# OLEDMiniFlyNRF.net
KiCad netlist of a schematic drawn in Altium Designer
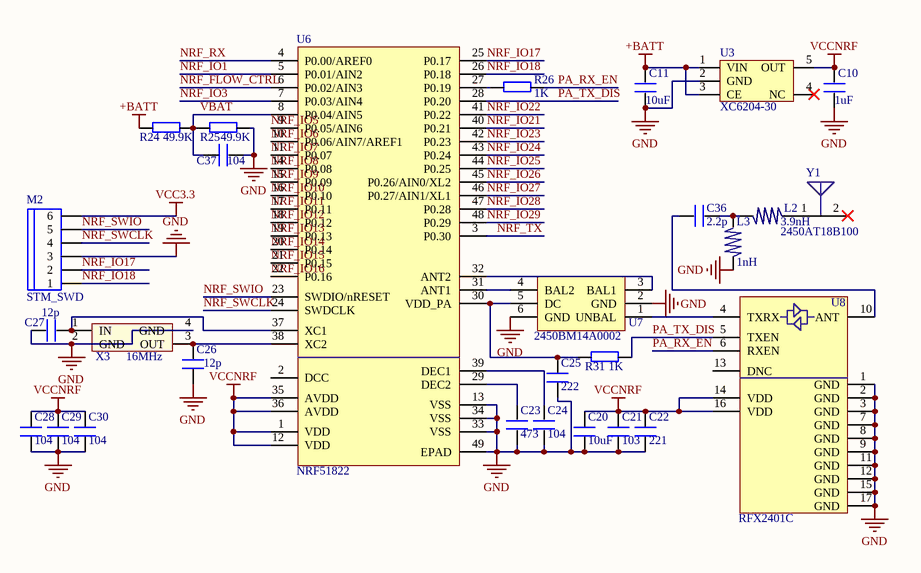
[diagram p0: OLEDMiniFlyNRF.SchDoc]

(export (version "E")
  (design (tool "Eeschema 10.0.6"))
  (components
    (comp (ref "C10") (value "1uF") (footprint "C 0603_L") (libsource (lib "ATK-2014-09-12") (part "C")))
    (comp (ref "C11") (value "10uF") (footprint "C 0603_L") (libsource (lib "ATK-2014-09-12") (part "C")))
    (comp (ref "C20") (value "10uF") (footprint "C 0603_L") (libsource (lib "ATK-2014-09-12") (part "C")))
    (comp (ref "C21") (value "103") (footprint "C 0603_L") (libsource (lib "ATK-2014-09-12") (part "C")))
    (comp (ref "C22") (value "221") (footprint "C 0603_L") (libsource (lib "ATK-2014-09-12") (part "C")))
    (comp (ref "C23") (value "473") (footprint "C 0603_L") (libsource (lib "ATK-2014-09-12") (part "C")))
    (comp (ref "C24") (value "104") (footprint "C 0603_L") (libsource (lib "ATK-2014-09-12") (part "C")))
    (comp (ref "C25") (value "222") (footprint "C 0603_L") (libsource (lib "ATK-2014-09-12") (part "C")))
    (comp (ref "C26") (value "12p") (footprint "C 0603_L") (libsource (lib "ATK-2014-09-12") (part "C")))
    (comp (ref "C27") (value "12p") (footprint "C 0603_L") (libsource (lib "ATK-2014-09-12") (part "C")))
    (comp (ref "C28") (value "104") (footprint "C 0603_L") (libsource (lib "ATK-2014-09-12") (part "C")))
    (comp (ref "C29") (value "104") (footprint "C 0603_L") (libsource (lib "ATK-2014-09-12") (part "C")))
    (comp (ref "C30") (value "104") (footprint "C 0603_L") (libsource (lib "ATK-2014-09-12") (part "C")))
    (comp (ref "C36") (value "2.2p") (footprint "0402") (libsource (lib "ATK-2014-09-12") (part "C")))
    (comp (ref "C37") (value "104") (footprint "C 0603_L") (libsource (lib "ATK-2014-09-12") (part "C")))
    (comp (ref "L2") (value "3.9nH") (footprint "0402") (libsource (lib "ATK-2014-09-12") (part "L")))
    (comp (ref "L3") (value "1nH") (footprint "0402") (libsource (lib "") (part "L_1")))
    (comp (ref "M2") (value "STM_SWD") (footprint "SH1.0_6P") (libsource (lib "MiniFly ") (part "HEAD6")))
    (comp (ref "R24") (value "49.9K") (footprint "R 0603_L") (libsource (lib "ATK-2014-09-12") (part "R")))
    (comp (ref "R25") (value "49.9K") (footprint "R 0603_L") (libsource (lib "ATK-2014-09-12") (part "R")))
    (comp (ref "R26") (value "1K") (footprint "R 0603_L") (libsource (lib "ATK-2014-09-12") (part "R")))
    (comp (ref "R31") (value "1K") (footprint "R 0603_L") (libsource (lib "ATK-2014-09-12") (part "R")))
    (comp (ref "U3")
      (value "XC6204-30")
      (footprint "SOT23-5L")
      (libsource (lib "ATK-2014-09-12") (part "XC6204"))
    )
    (comp (ref "U6")
      (value "NRF51822")
      (footprint "QFN48M-04")
      (libsource (lib "ATK-2014-09-12") (part "NRF51822"))
    )
    (comp (ref "U7")
      (value "2450BM14A0002")
      (footprint "0603-6")
      (libsource (lib "ATK-2014-09-12") (part "BALUN"))
    )
    (comp (ref "U8")
      (value "RFX2401C")
      (footprint "QFN16M")
      (libsource (lib "ATK-2014-09-12") (part "RFX2401C"))
    )
    (comp (ref "X3")
      (value "16MHz")
      (footprint "OSC32254Pmini")
      (description "无源贴片晶振")
      (libsource (lib "ATK-2014-09-12") (part "XTAL-无源贴片"))
    )
    (comp (ref "Y1")
      (value "2450AT18B100")
      (footprint "L 1206")
      (libsource (lib "ATK-2014-09-12") (part "CHIP_ANTENNA"))
    )
  )
  (nets
    (net (code "1") (name "+BATT") (class "Default")
      (node (ref "C11") (pin "2") (pintype "passive"))
      (node (ref "R24") (pin "2") (pintype "passive"))
      (node (ref "U3") (pin "1") (pinfunction "VIN_1") (pintype "passive"))
      (node (ref "U3") (pin "3") (pinfunction "CE_3") (pintype "passive"))
    )
    (net (code "2") (name "/NRF_FLOW_CTRL") (class "Default")
      (node (ref "U6") (pin "6") (pinfunction "P0.02/AIN3_6") (pintype "passive"))
    )
    (net (code "3") (name "/NRF_IO1") (class "Default")
      (node (ref "U6") (pin "5") (pinfunction "P0.01/AIN2_5") (pintype "passive"))
    )
    (net (code "4") (name "/NRF_IO3") (class "Default")
      (node (ref "U6") (pin "7") (pinfunction "P0.03/AIN4_7") (pintype "passive"))
    )
    (net (code "5") (name "/NRF_IO5") (class "Default")
      (node (ref "U6") (pin "9") (pinfunction "P0.05/AIN6_9") (pintype "passive"))
    )
    (net (code "6") (name "/NRF_IO6") (class "Default")
      (node (ref "U6") (pin "10") (pinfunction "P0.06/AIN7/AREF1_10") (pintype "passive"))
    )
    (net (code "7") (name "/NRF_IO7") (class "Default")
      (node (ref "U6") (pin "11") (pinfunction "P0.07_11") (pintype "passive"))
    )
    (net (code "8") (name "/NRF_IO8") (class "Default")
      (node (ref "U6") (pin "14") (pinfunction "P0.08_14") (pintype "passive"))
    )
    (net (code "9") (name "/NRF_IO9") (class "Default")
      (node (ref "U6") (pin "15") (pinfunction "P0.09_15") (pintype "passive"))
    )
    (net (code "10") (name "/NRF_IO10") (class "Default")
      (node (ref "U6") (pin "16") (pinfunction "P0.10_16") (pintype "passive"))
    )
    (net (code "11") (name "/NRF_IO11") (class "Default")
      (node (ref "U6") (pin "17") (pinfunction "P0.11_17") (pintype "passive"))
    )
    (net (code "12") (name "/NRF_IO12") (class "Default")
      (node (ref "U6") (pin "18") (pinfunction "P0.12_18") (pintype "passive"))
    )
    (net (code "13") (name "/NRF_IO13") (class "Default")
      (node (ref "U6") (pin "19") (pinfunction "P0.13_19") (pintype "passive"))
    )
    (net (code "14") (name "/NRF_IO14") (class "Default")
      (node (ref "U6") (pin "20") (pinfunction "P0.14_20") (pintype "passive"))
    )
    (net (code "15") (name "/NRF_IO15") (class "Default")
      (node (ref "U6") (pin "21") (pinfunction "P0.15_21") (pintype "passive"))
    )
    (net (code "16") (name "/NRF_IO16") (class "Default")
      (node (ref "U6") (pin "22") (pinfunction "P0.16_22") (pintype "passive"))
    )
    (net (code "17") (name "/NRF_IO17") (class "Default")
      (node (ref "M2") (pin "2") (pinfunction "2_2") (pintype "passive"))
      (node (ref "U6") (pin "25") (pinfunction "P0.17_25") (pintype "passive"))
    )
    (net (code "18") (name "/NRF_IO18") (class "Default")
      (node (ref "M2") (pin "1") (pinfunction "1_1") (pintype "passive"))
      (node (ref "U6") (pin "26") (pinfunction "P0.18_26") (pintype "passive"))
    )
    (net (code "19") (name "/NRF_IO21") (class "Default")
      (node (ref "U6") (pin "40") (pinfunction "P0.21_40") (pintype "passive"))
    )
    (net (code "20") (name "/NRF_IO22") (class "Default")
      (node (ref "U6") (pin "41") (pinfunction "P0.22_41") (pintype "passive"))
    )
    (net (code "21") (name "/NRF_IO23") (class "Default")
      (node (ref "U6") (pin "42") (pinfunction "P0.23_42") (pintype "passive"))
    )
    (net (code "22") (name "/NRF_IO24") (class "Default")
      (node (ref "U6") (pin "43") (pinfunction "P0.24_43") (pintype "passive"))
    )
    (net (code "23") (name "/NRF_IO25") (class "Default")
      (node (ref "U6") (pin "44") (pinfunction "P0.25_44") (pintype "passive"))
    )
    (net (code "24") (name "/NRF_IO26") (class "Default")
      (node (ref "U6") (pin "45") (pinfunction "P0.26/AIN0/XL2_45") (pintype "passive"))
    )
    (net (code "25") (name "/NRF_IO27") (class "Default")
      (node (ref "U6") (pin "46") (pinfunction "P0.27/AIN1/XL1_46") (pintype "passive"))
    )
    (net (code "26") (name "/NRF_IO28") (class "Default")
      (node (ref "U6") (pin "47") (pinfunction "P0.28_47") (pintype "passive"))
    )
    (net (code "27") (name "/NRF_IO29") (class "Default")
      (node (ref "U6") (pin "48") (pinfunction "P0.29_48") (pintype "passive"))
    )
    (net (code "28") (name "/NRF_RX") (class "Default")
      (node (ref "U6") (pin "4") (pinfunction "P0.00/AREF0_4") (pintype "passive"))
    )
    (net (code "29") (name "/NRF_SWCLK") (class "Default")
      (node (ref "M2") (pin "4") (pinfunction "4_4") (pintype "passive"))
      (node (ref "U6") (pin "24") (pinfunction "SWDCLK_24") (pintype "passive"))
    )
    (net (code "30") (name "/NRF_SWIO") (class "Default")
      (node (ref "M2") (pin "5") (pinfunction "5_5") (pintype "passive"))
      (node (ref "U6") (pin "23") (pinfunction "SWDIO/nRESET_23") (pintype "passive"))
    )
    (net (code "31") (name "/NRF_TX") (class "Default")
      (node (ref "U6") (pin "3") (pinfunction "P0.30_3") (pintype "passive"))
    )
    (net (code "32") (name "/PA_RX_EN") (class "Default")
      (node (ref "R26") (pin "1") (pintype "passive"))
      (node (ref "U8") (pin "6") (pinfunction "RXEN_6") (pintype "passive"))
    )
    (net (code "33") (name "/PA_TX_DIS") (class "Default")
      (node (ref "R31") (pin "1") (pintype "passive"))
      (node (ref "U6") (pin "28") (pinfunction "P0.20_28") (pintype "passive"))
      (node (ref "U8") (pin "5") (pinfunction "TXEN_5") (pintype "passive"))
    )
    (net (code "34") (name "/VBAT") (class "Default")
      (node (ref "C37") (pin "2") (pintype "passive"))
      (node (ref "R24") (pin "1") (pintype "passive"))
      (node (ref "R25") (pin "2") (pintype "passive"))
      (node (ref "U6") (pin "8") (pinfunction "P0.04/AIN5_8") (pintype "passive"))
    )
    (net (code "35") (name "GND") (class "Default")
      (node (ref "C10") (pin "1") (pintype "passive"))
      (node (ref "C11") (pin "1") (pintype "passive"))
      (node (ref "C20") (pin "2") (pintype "passive"))
      (node (ref "C21") (pin "2") (pintype "passive"))
      (node (ref "C22") (pin "2") (pintype "passive"))
      (node (ref "C23") (pin "2") (pintype "passive"))
      (node (ref "C24") (pin "2") (pintype "passive"))
      (node (ref "C25") (pin "2") (pintype "passive"))
      (node (ref "C26") (pin "1") (pintype "passive"))
      (node (ref "C27") (pin "2") (pintype "passive"))
      (node (ref "C28") (pin "2") (pintype "passive"))
      (node (ref "C29") (pin "2") (pintype "passive"))
      (node (ref "C30") (pin "2") (pintype "passive"))
      (node (ref "C37") (pin "1") (pintype "passive"))
      (node (ref "L3") (pin "2") (pintype "passive"))
      (node (ref "M2") (pin "3") (pinfunction "3_3") (pintype "passive"))
      (node (ref "R25") (pin "1") (pintype "passive"))
      (node (ref "U3") (pin "2") (pinfunction "GND_2") (pintype "passive"))
      (node (ref "U6") (pin "13") (pinfunction "VSS_13") (pintype "passive"))
      (node (ref "U6") (pin "33") (pinfunction "VSS_33") (pintype "passive"))
      (node (ref "U6") (pin "34") (pinfunction "VSS_34") (pintype "passive"))
      (node (ref "U6") (pin "49") (pinfunction "EPAD_49") (pintype "passive"))
      (node (ref "U7") (pin "2") (pinfunction "GND_2") (pintype "passive"))
      (node (ref "U7") (pin "6") (pinfunction "GND_6") (pintype "passive"))
      (node (ref "U8") (pin "1") (pinfunction "GND_1") (pintype "passive"))
      (node (ref "U8") (pin "11") (pinfunction "GND_11") (pintype "passive"))
      (node (ref "U8") (pin "12") (pinfunction "GND_12") (pintype "passive"))
      (node (ref "U8") (pin "15") (pinfunction "GND_15") (pintype "passive"))
      (node (ref "U8") (pin "17") (pinfunction "GND_17") (pintype "passive"))
      (node (ref "U8") (pin "2") (pinfunction "GND_2") (pintype "passive"))
      (node (ref "U8") (pin "3") (pinfunction "GND_3") (pintype "passive"))
      (node (ref "U8") (pin "7") (pinfunction "GND_7") (pintype "passive"))
      (node (ref "U8") (pin "8") (pinfunction "GND_8") (pintype "passive"))
      (node (ref "U8") (pin "9") (pinfunction "GND_9") (pintype "passive"))
      (node (ref "X3") (pin "2") (pinfunction "GND_2") (pintype "passive"))
      (node (ref "X3") (pin "4") (pinfunction "GND_4") (pintype "passive"))
    )
    (net (code "36") (name "Net-(C36-Pad2)") (class "Default")
      (node (ref "C36") (pin "2") (pintype "passive"))
      (node (ref "L2") (pin "2") (pintype "passive"))
      (node (ref "L3") (pin "1") (pintype "passive"))
    )
    (net (code "37") (name "Net-(U6-ANT1)") (class "Default")
      (node (ref "U6") (pin "31") (pinfunction "ANT1_31") (pintype "passive"))
      (node (ref "U7") (pin "4") (pinfunction "BAL2_4") (pintype "passive"))
    )
    (net (code "38") (name "Net-(U6-ANT2)") (class "Default")
      (node (ref "U6") (pin "32") (pinfunction "ANT2_32") (pintype "passive"))
      (node (ref "U7") (pin "3") (pinfunction "BAL1_3") (pintype "passive"))
    )
    (net (code "39") (name "Net-(U6-DEC1)") (class "Default")
      (node (ref "C24") (pin "1") (pintype "passive"))
      (node (ref "U6") (pin "39") (pinfunction "DEC1_39") (pintype "passive"))
    )
    (net (code "40") (name "Net-(U6-DEC2)") (class "Default")
      (node (ref "C23") (pin "1") (pintype "passive"))
      (node (ref "U6") (pin "29") (pinfunction "DEC2_29") (pintype "passive"))
    )
    (net (code "41") (name "Net-(U6-P0.19)") (class "Default")
      (node (ref "R26") (pin "2") (pintype "passive"))
      (node (ref "U6") (pin "27") (pinfunction "P0.19_27") (pintype "passive"))
    )
    (net (code "42") (name "Net-(U6-VDD_PA)") (class "Default")
      (node (ref "C25") (pin "1") (pintype "passive"))
      (node (ref "R31") (pin "2") (pintype "passive"))
      (node (ref "U6") (pin "30") (pinfunction "VDD_PA_30") (pintype "passive"))
      (node (ref "U7") (pin "5") (pinfunction "DC_5") (pintype "passive"))
    )
    (net (code "43") (name "Net-(U6-XC1)") (class "Default")
      (node (ref "C27") (pin "1") (pintype "passive"))
      (node (ref "U6") (pin "37") (pinfunction "XC1_37") (pintype "passive"))
      (node (ref "X3") (pin "1") (pinfunction "IN_1") (pintype "passive"))
    )
    (net (code "44") (name "Net-(U6-XC2)") (class "Default")
      (node (ref "C26") (pin "2") (pintype "passive"))
      (node (ref "U6") (pin "38") (pinfunction "XC2_38") (pintype "passive"))
      (node (ref "X3") (pin "3") (pinfunction "OUT_3") (pintype "passive"))
    )
    (net (code "45") (name "Net-(U7-UNBAL)") (class "Default")
      (node (ref "U7") (pin "1") (pinfunction "UNBAL_1") (pintype "passive"))
      (node (ref "U8") (pin "4") (pinfunction "TXRX_4") (pintype "passive"))
    )
    (net (code "46") (name "Net-(U8-ANT)") (class "Default")
      (node (ref "C36") (pin "1") (pintype "passive"))
      (node (ref "U8") (pin "10") (pinfunction "ANT_10") (pintype "passive"))
    )
    (net (code "47") (name "Net-(Y1-FP)") (class "Default")
      (node (ref "L2") (pin "1") (pintype "passive"))
      (node (ref "Y1") (pin "1") (pinfunction "FP_1") (pintype "passive"))
    )
    (net (code "48") (name "VCC3.3") (class "Default")
      (node (ref "M2") (pin "6") (pinfunction "6_6") (pintype "passive"))
    )
    (net (code "49") (name "VCCNRF") (class "Default")
      (node (ref "C10") (pin "2") (pintype "passive"))
      (node (ref "C20") (pin "1") (pintype "passive"))
      (node (ref "C21") (pin "1") (pintype "passive"))
      (node (ref "C22") (pin "1") (pintype "passive"))
      (node (ref "C28") (pin "1") (pintype "passive"))
      (node (ref "C29") (pin "1") (pintype "passive"))
      (node (ref "C30") (pin "1") (pintype "passive"))
      (node (ref "U3") (pin "5") (pinfunction "OUT_5") (pintype "passive"))
      (node (ref "U6") (pin "1") (pinfunction "VDD_1") (pintype "passive"))
      (node (ref "U6") (pin "12") (pinfunction "VDD_12") (pintype "passive"))
      (node (ref "U6") (pin "35") (pinfunction "AVDD_35") (pintype "passive"))
      (node (ref "U6") (pin "36") (pinfunction "AVDD_36") (pintype "passive"))
      (node (ref "U8") (pin "14") (pinfunction "VDD_14") (pintype "passive"))
      (node (ref "U8") (pin "16") (pinfunction "VDD_16") (pintype "passive"))
    )
    (net (code "50") (name "unconnected-(U3-NC-Pad4)") (class "Default")
      (node (ref "U3") (pin "4") (pinfunction "NC_4") (pintype "passive+no_connect"))
    )
    (net (code "51") (name "unconnected-(U6-DCC-Pad2)") (class "Default")
      (node (ref "U6") (pin "2") (pinfunction "DCC_2") (pintype "passive"))
    )
    (net (code "52") (name "unconnected-(U8-DNC-Pad13)") (class "Default")
      (node (ref "U8") (pin "13") (pinfunction "DNC_13") (pintype "passive"))
    )
    (net (code "53") (name "unconnected-(Y1-NC-Pad2)") (class "Default")
      (node (ref "Y1") (pin "2") (pinfunction "NC_2") (pintype "passive+no_connect"))
    )
  )
)
